# 51_board.net
KiCad netlist of a schematic drawn in Altium Designer
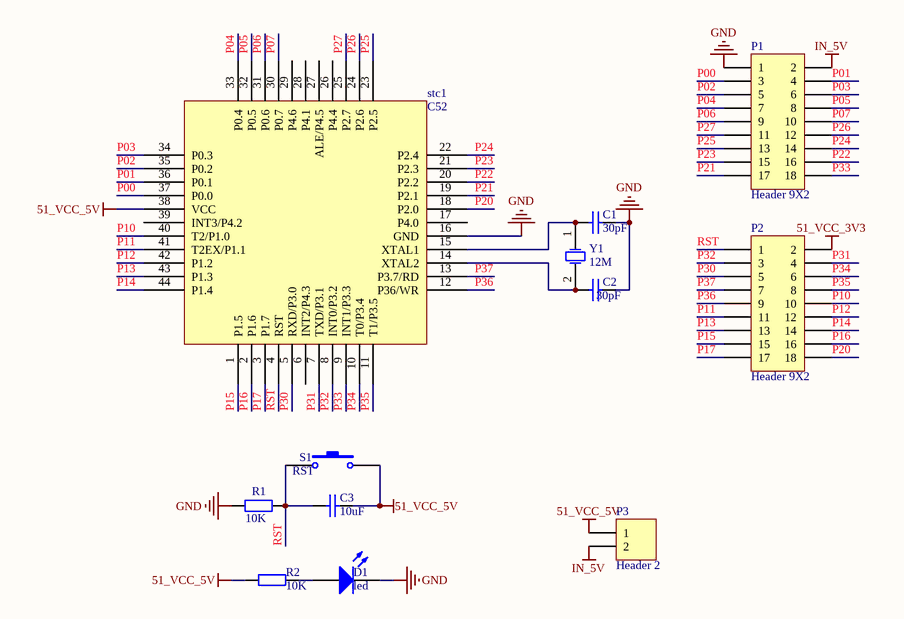
[diagram p0: 51_board.SchDoc]

(export (version "E")
  (design (tool "Eeschema 10.0.6"))
  (components
    (comp (ref "C1")
      (value "30pF")
      (footprint "6-0805_N")
      (description "Capacitor")
      (fields (field (name "PUBLISHER") "Altium Limited"))
      (libsource (lib "Miscellaneous Devices") (part "Cap"))
    )
    (comp (ref "C2")
      (value "30pF")
      (footprint "6-0805_N")
      (description "Capacitor")
      (fields (field (name "PUBLISHER") "Altium Limited"))
      (libsource (lib "Miscellaneous Devices") (part "Cap"))
    )
    (comp (ref "C3")
      (value "10uF")
      (footprint "6-0805_N")
      (description "Capacitor")
      (fields (field (name "PUBLISHER") "Altium Limited"))
      (libsource (lib "Miscellaneous Devices") (part "Cap"))
    )
    (comp (ref "D1")
      (value "led")
      (footprint "LED")
      (description "Typical INFRARED GaAs LED")
      (fields (field (name "PUBLISHER") "Altium Limited"))
      (libsource (lib "Miscellaneous Devices") (part "LED0"))
    )
    (comp (ref "P1")
      (value "Header 9X2")
      (footprint "XDR2x9")
      (description "Header, 9-Pin, Dual row")
      (fields (field (name "PUBLISHER") "Altium Limited"))
      (libsource (lib "Miscellaneous Connectors") (part "Header 9X2"))
    )
    (comp (ref "P2")
      (value "Header 9X2")
      (footprint "XDR2x9")
      (description "Header, 9-Pin, Dual row")
      (fields (field (name "PUBLISHER") "Altium Limited"))
      (libsource (lib "Miscellaneous Connectors") (part "Header 9X2"))
    )
    (comp (ref "P3")
      (value "Header 2")
      (footprint "HDR1X2")
      (description "Header, 2-Pin")
      (fields (field (name "PUBLISHER") "Altium Limited"))
      (libsource (lib "Miscellaneous Connectors") (part "Header 2"))
    )
    (comp (ref "R1")
      (value "10K")
      (footprint "6-0805_N")
      (description "Resistor")
      (fields (field (name "PUBLISHER") "Altium Limited"))
      (libsource (lib "Miscellaneous Devices") (part "Res2"))
    )
    (comp (ref "R2")
      (value "10K")
      (footprint "6-0805_N")
      (description "Resistor")
      (fields (field (name "PUBLISHER") "Altium Limited"))
      (libsource (lib "Miscellaneous Devices") (part "Res2"))
    )
    (comp (ref "S1")
      (value "RST")
      (footprint "SPST-2")
      (description "Switch")
      (fields (field (name "PUBLISHER") "Altium Limited"))
      (libsource (lib "Miscellaneous Devices") (part "SW-PB"))
    )
    (comp (ref "stc1") (value "C52") (footprint "LQFP44") (libsource (lib "Schlib1") (part "C52")))
    (comp (ref "Y1")
      (value "12M")
      (footprint "HC-49S")
      (description "Crystal Oscillator")
      (fields (field (name "PUBLISHER") "Altium Limited"))
      (libsource (lib "Miscellaneous Devices") (part "XTAL"))
    )
  )
  (nets
    (net (code "1") (name "/P00") (class "Default")
      (node (ref "P1") (pin "3") (pinfunction "3_3") (pintype "passive"))
      (node (ref "stc1") (pin "37") (pinfunction "P0.0_37") (pintype "passive"))
    )
    (net (code "2") (name "/P01") (class "Default")
      (node (ref "P1") (pin "4") (pinfunction "4_4") (pintype "passive"))
      (node (ref "stc1") (pin "36") (pinfunction "P0.1_36") (pintype "passive"))
    )
    (net (code "3") (name "/P02") (class "Default")
      (node (ref "P1") (pin "5") (pinfunction "5_5") (pintype "passive"))
      (node (ref "stc1") (pin "35") (pinfunction "P0.2_35") (pintype "passive"))
    )
    (net (code "4") (name "/P03") (class "Default")
      (node (ref "P1") (pin "6") (pinfunction "6_6") (pintype "passive"))
      (node (ref "stc1") (pin "34") (pinfunction "P0.3_34") (pintype "passive"))
    )
    (net (code "5") (name "/P04") (class "Default")
      (node (ref "P1") (pin "7") (pinfunction "7_7") (pintype "passive"))
      (node (ref "stc1") (pin "33") (pinfunction "P0.4_33") (pintype "passive"))
    )
    (net (code "6") (name "/P05") (class "Default")
      (node (ref "P1") (pin "8") (pinfunction "8_8") (pintype "passive"))
      (node (ref "stc1") (pin "32") (pinfunction "P0.5_32") (pintype "passive"))
    )
    (net (code "7") (name "/P06") (class "Default")
      (node (ref "P1") (pin "9") (pinfunction "9_9") (pintype "passive"))
      (node (ref "stc1") (pin "31") (pinfunction "P0.6_31") (pintype "passive"))
    )
    (net (code "8") (name "/P07") (class "Default")
      (node (ref "P1") (pin "10") (pinfunction "10_10") (pintype "passive"))
      (node (ref "stc1") (pin "30") (pinfunction "P0.7_30") (pintype "passive"))
    )
    (net (code "9") (name "/P10") (class "Default")
      (node (ref "P2") (pin "10") (pinfunction "10_10") (pintype "passive"))
      (node (ref "stc1") (pin "40") (pinfunction "T2/P1.0_40") (pintype "passive"))
    )
    (net (code "10") (name "/P11") (class "Default")
      (node (ref "P2") (pin "11") (pinfunction "11_11") (pintype "passive"))
      (node (ref "stc1") (pin "41") (pinfunction "T2EX/P1.1_41") (pintype "passive"))
    )
    (net (code "11") (name "/P12") (class "Default")
      (node (ref "P2") (pin "12") (pinfunction "12_12") (pintype "passive"))
      (node (ref "stc1") (pin "42") (pinfunction "P1.2_42") (pintype "passive"))
    )
    (net (code "12") (name "/P13") (class "Default")
      (node (ref "P2") (pin "13") (pinfunction "13_13") (pintype "passive"))
      (node (ref "stc1") (pin "43") (pinfunction "P1.3_43") (pintype "passive"))
    )
    (net (code "13") (name "/P14") (class "Default")
      (node (ref "P2") (pin "14") (pinfunction "14_14") (pintype "passive"))
      (node (ref "stc1") (pin "44") (pinfunction "P1.4_44") (pintype "passive"))
    )
    (net (code "14") (name "/P15") (class "Default")
      (node (ref "P2") (pin "15") (pinfunction "15_15") (pintype "passive"))
      (node (ref "stc1") (pin "1") (pinfunction "P1.5_1") (pintype "passive"))
    )
    (net (code "15") (name "/P16") (class "Default")
      (node (ref "P2") (pin "16") (pinfunction "16_16") (pintype "passive"))
      (node (ref "stc1") (pin "2") (pinfunction "P1.6_2") (pintype "passive"))
    )
    (net (code "16") (name "/P17") (class "Default")
      (node (ref "P2") (pin "17") (pinfunction "17_17") (pintype "passive"))
      (node (ref "stc1") (pin "3") (pinfunction "P1.7_3") (pintype "passive"))
    )
    (net (code "17") (name "/P20") (class "Default")
      (node (ref "P2") (pin "18") (pinfunction "18_18") (pintype "passive"))
      (node (ref "stc1") (pin "18") (pinfunction "P2.0_18") (pintype "passive"))
    )
    (net (code "18") (name "/P21") (class "Default")
      (node (ref "P1") (pin "17") (pinfunction "17_17") (pintype "passive"))
      (node (ref "stc1") (pin "19") (pinfunction "P2.1_19") (pintype "passive"))
    )
    (net (code "19") (name "/P22") (class "Default")
      (node (ref "P1") (pin "16") (pinfunction "16_16") (pintype "passive"))
      (node (ref "stc1") (pin "20") (pinfunction "P2.2_20") (pintype "passive"))
    )
    (net (code "20") (name "/P23") (class "Default")
      (node (ref "P1") (pin "15") (pinfunction "15_15") (pintype "passive"))
      (node (ref "stc1") (pin "21") (pinfunction "P2.3_21") (pintype "passive"))
    )
    (net (code "21") (name "/P24") (class "Default")
      (node (ref "P1") (pin "14") (pinfunction "14_14") (pintype "passive"))
      (node (ref "stc1") (pin "22") (pinfunction "P2.4_22") (pintype "passive"))
    )
    (net (code "22") (name "/P25") (class "Default")
      (node (ref "P1") (pin "13") (pinfunction "13_13") (pintype "passive"))
      (node (ref "stc1") (pin "23") (pinfunction "P2.5_23") (pintype "passive"))
    )
    (net (code "23") (name "/P26") (class "Default")
      (node (ref "P1") (pin "12") (pinfunction "12_12") (pintype "passive"))
      (node (ref "stc1") (pin "24") (pinfunction "P2.6_24") (pintype "passive"))
    )
    (net (code "24") (name "/P27") (class "Default")
      (node (ref "P1") (pin "11") (pinfunction "11_11") (pintype "passive"))
      (node (ref "stc1") (pin "25") (pinfunction "P2.7_25") (pintype "passive"))
    )
    (net (code "25") (name "/P30") (class "Default")
      (node (ref "P2") (pin "5") (pinfunction "5_5") (pintype "passive"))
      (node (ref "stc1") (pin "5") (pinfunction "RXD/P3.0_5") (pintype "passive"))
    )
    (net (code "26") (name "/P31") (class "Default")
      (node (ref "P2") (pin "4") (pinfunction "4_4") (pintype "passive"))
      (node (ref "stc1") (pin "7") (pinfunction "TXD/P3.1_7") (pintype "passive"))
    )
    (net (code "27") (name "/P32") (class "Default")
      (node (ref "P2") (pin "3") (pinfunction "3_3") (pintype "passive"))
      (node (ref "stc1") (pin "8") (pinfunction "INT0/P3.2_8") (pintype "passive"))
    )
    (net (code "28") (name "/P33") (class "Default")
      (node (ref "P1") (pin "18") (pinfunction "18_18") (pintype "passive"))
      (node (ref "stc1") (pin "9") (pinfunction "INT1/P3.3_9") (pintype "passive"))
    )
    (net (code "29") (name "/P34") (class "Default")
      (node (ref "P2") (pin "6") (pinfunction "6_6") (pintype "passive"))
      (node (ref "stc1") (pin "10") (pinfunction "T0/P3.4_10") (pintype "passive"))
    )
    (net (code "30") (name "/P35") (class "Default")
      (node (ref "P2") (pin "8") (pinfunction "8_8") (pintype "passive"))
      (node (ref "stc1") (pin "11") (pinfunction "T1/P3.5_11") (pintype "passive"))
    )
    (net (code "31") (name "/P36") (class "Default")
      (node (ref "P2") (pin "9") (pinfunction "9_9") (pintype "passive"))
      (node (ref "stc1") (pin "12") (pinfunction "P36/WR_12") (pintype "passive"))
    )
    (net (code "32") (name "/P37") (class "Default")
      (node (ref "P2") (pin "7") (pinfunction "7_7") (pintype "passive"))
      (node (ref "stc1") (pin "13") (pinfunction "P3.7/RD_13") (pintype "passive"))
    )
    (net (code "33") (name "/RST") (class "Default")
      (node (ref "C3") (pin "1") (pinfunction "1_1") (pintype "passive"))
      (node (ref "P2") (pin "1") (pinfunction "1_1") (pintype "passive"))
      (node (ref "R1") (pin "2") (pinfunction "2_2") (pintype "passive"))
      (node (ref "S1") (pin "1") (pinfunction "1_1") (pintype "passive"))
      (node (ref "stc1") (pin "4") (pinfunction "RST_4") (pintype "passive"))
    )
    (net (code "34") (name "51_VCC_3V3") (class "Default")
      (node (ref "P2") (pin "2") (pinfunction "2_2") (pintype "passive"))
    )
    (net (code "35") (name "51_VCC_5V") (class "Default")
      (node (ref "C3") (pin "2") (pinfunction "2_2") (pintype "passive"))
      (node (ref "P3") (pin "1") (pinfunction "1_1") (pintype "passive"))
      (node (ref "R2") (pin "1") (pinfunction "1_1") (pintype "passive"))
      (node (ref "S1") (pin "2") (pinfunction "2_2") (pintype "passive"))
      (node (ref "stc1") (pin "38") (pinfunction "VCC_38") (pintype "passive"))
    )
    (net (code "36") (name "GND") (class "Default")
      (node (ref "C1") (pin "1") (pinfunction "1_1") (pintype "passive"))
      (node (ref "C2") (pin "1") (pinfunction "1_1") (pintype "passive"))
      (node (ref "D1") (pin "2") (pinfunction "K_2") (pintype "passive"))
      (node (ref "P1") (pin "1") (pinfunction "1_1") (pintype "passive"))
      (node (ref "R1") (pin "1") (pinfunction "1_1") (pintype "passive"))
      (node (ref "stc1") (pin "16") (pinfunction "GND_16") (pintype "passive"))
    )
    (net (code "37") (name "IN_5V") (class "Default")
      (node (ref "P1") (pin "2") (pinfunction "2_2") (pintype "passive"))
      (node (ref "P3") (pin "2") (pinfunction "2_2") (pintype "passive"))
    )
    (net (code "38") (name "Net-(D1-A)") (class "Default")
      (node (ref "D1") (pin "1") (pinfunction "A_1") (pintype "passive"))
      (node (ref "R2") (pin "2") (pinfunction "2_2") (pintype "passive"))
    )
    (net (code "39") (name "Net-(Y1-OSC1)") (class "Default")
      (node (ref "C1") (pin "2") (pinfunction "2_2") (pintype "passive"))
      (node (ref "Y1") (pin "1") (pinfunction "OSC1_1") (pintype "passive"))
      (node (ref "stc1") (pin "15") (pinfunction "XTAL1_15") (pintype "passive"))
    )
    (net (code "40") (name "Net-(Y1-OSC2)") (class "Default")
      (node (ref "C2") (pin "2") (pinfunction "2_2") (pintype "passive"))
      (node (ref "Y1") (pin "2") (pinfunction "OSC2_2") (pintype "passive"))
      (node (ref "stc1") (pin "14") (pinfunction "XTAL2_14") (pintype "passive"))
    )
    (net (code "41") (name "unconnected-(stc1-ALE{slash}P4.5-Pad27)") (class "Default")
      (node (ref "stc1") (pin "27") (pinfunction "ALE/P4.5_27") (pintype "passive"))
    )
    (net (code "42") (name "unconnected-(stc1-INT2{slash}P4.3-Pad6)") (class "Default")
      (node (ref "stc1") (pin "6") (pinfunction "INT2/P4.3_6") (pintype "passive"))
    )
    (net (code "43") (name "unconnected-(stc1-INT3{slash}P4.2-Pad39)") (class "Default")
      (node (ref "stc1") (pin "39") (pinfunction "INT3/P4.2_39") (pintype "passive"))
    )
    (net (code "44") (name "unconnected-(stc1-P4.0-Pad17)") (class "Default")
      (node (ref "stc1") (pin "17") (pinfunction "P4.0_17") (pintype "passive"))
    )
    (net (code "45") (name "unconnected-(stc1-P4.1-Pad28)") (class "Default")
      (node (ref "stc1") (pin "28") (pinfunction "P4.1_28") (pintype "passive"))
    )
    (net (code "46") (name "unconnected-(stc1-P4.4-Pad26)") (class "Default")
      (node (ref "stc1") (pin "26") (pinfunction "P4.4_26") (pintype "passive"))
    )
    (net (code "47") (name "unconnected-(stc1-P4.6-Pad29)") (class "Default")
      (node (ref "stc1") (pin "29") (pinfunction "P4.6_29") (pintype "passive"))
    )
  )
)
